# GPS_Board_Rev_B.net
KiCad netlist of a schematic drawn in EAGLE
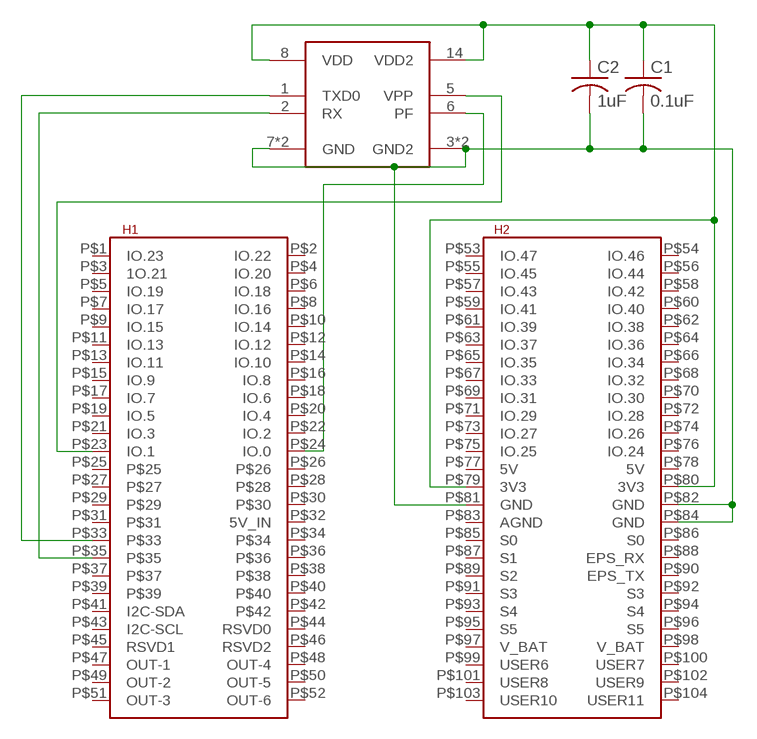
[diagram p0: schematic, sheet 1]

(export (version "E")
  (design (tool "Eeschema 10.0.6"))
  (components
    (comp (ref "C1")
      (value "0.1uF")
      (footprint "eagle-import:C0603")
      (libsource (lib "eagle-import") (part "C-USC0603"))
    )
    (comp (ref "C2")
      (value "1uF")
      (footprint "eagle-import:C0603")
      (libsource (lib "eagle-import") (part "C-USC0603"))
    )
    (comp (ref "U$1")
      (value "PINAVL1")
      (footprint "eagle-import:PINAV-L1")
      (libsource (lib "eagle-import") (part "PINAVL1"))
    )
    (comp (ref "U$2")
      (value "PC104")
      (footprint "eagle-import:PC104")
      (libsource (lib "eagle-import") (part "PC104"))
    )
  )
  (nets
    (net (code "1") (name "Net-(C1-Pad2)") (class "Default")
      (node (ref "C1") (pin "2") (pinfunction "2_2") (pintype "passive"))
      (node (ref "C2") (pin "2") (pinfunction "2_2") (pintype "passive"))
      (node (ref "U$1") (pin "15") (pinfunction "GND2_15") (pintype "bidirectional"))
      (node (ref "U$1") (pin "16") (pinfunction "GND_16") (pintype "bidirectional"))
      (node (ref "U$1") (pin "3") (pinfunction "GND2_3") (pintype "bidirectional"))
      (node (ref "U$1") (pin "7") (pinfunction "GND_7") (pintype "bidirectional"))
      (node (ref "U$2") (pin "P$81") (pinfunction "GND_P$81") (pintype "bidirectional"))
      (node (ref "U$2") (pin "P$82") (pinfunction "GND_P$82") (pintype "bidirectional"))
      (node (ref "U$2") (pin "P$84") (pinfunction "GND_P$84") (pintype "bidirectional"))
    )
    (net (code "2") (name "Net-(U$1-PF)") (class "Default")
      (node (ref "U$1") (pin "6") (pinfunction "PF_6") (pintype "bidirectional"))
      (node (ref "U$2") (pin "P$24") (pinfunction "IO.0_P$24") (pintype "bidirectional"))
    )
    (net (code "3") (name "Net-(U$1-RX)") (class "Default")
      (node (ref "U$1") (pin "2") (pinfunction "RX_2") (pintype "bidirectional"))
      (node (ref "U$2") (pin "P$35") (pinfunction "P$35_P$35") (pintype "bidirectional"))
    )
    (net (code "4") (name "Net-(U$1-TXD0)") (class "Default")
      (node (ref "U$1") (pin "1") (pinfunction "TXD0_1") (pintype "bidirectional"))
      (node (ref "U$2") (pin "P$33") (pinfunction "P$33_P$33") (pintype "bidirectional"))
    )
    (net (code "5") (name "Net-(U$1-VDD)") (class "Default")
      (node (ref "C1") (pin "1") (pinfunction "1_1") (pintype "passive"))
      (node (ref "C2") (pin "1") (pinfunction "1_1") (pintype "passive"))
      (node (ref "U$1") (pin "14") (pinfunction "VDD2_14") (pintype "bidirectional"))
      (node (ref "U$1") (pin "8") (pinfunction "VDD_8") (pintype "bidirectional"))
      (node (ref "U$2") (pin "P$79") (pinfunction "3V3_P$79") (pintype "bidirectional"))
      (node (ref "U$2") (pin "P$80") (pinfunction "3V3_P$80") (pintype "bidirectional"))
    )
    (net (code "6") (name "Net-(U$1-VPP)") (class "Default")
      (node (ref "U$1") (pin "5") (pinfunction "VPP_5") (pintype "bidirectional"))
      (node (ref "U$2") (pin "P$23") (pinfunction "IO.1_P$23") (pintype "bidirectional"))
    )
    (net (code "7") (name "unconnected-(U$2-1O.21-PadP$3)") (class "Default")
      (node (ref "U$2") (pin "P$3") (pinfunction "1O.21_P$3") (pintype "bidirectional"))
    )
    (net (code "8") (name "unconnected-(U$2-5V-PadP$77)") (class "Default")
      (node (ref "U$2") (pin "P$77") (pinfunction "5V_P$77") (pintype "bidirectional"))
    )
    (net (code "9") (name "unconnected-(U$2-5V-PadP$78)") (class "Default")
      (node (ref "U$2") (pin "P$78") (pinfunction "5V_P$78") (pintype "bidirectional"))
    )
    (net (code "10") (name "unconnected-(U$2-5V_IN-PadP$32)") (class "Default")
      (node (ref "U$2") (pin "P$32") (pinfunction "5V_IN_P$32") (pintype "bidirectional"))
    )
    (net (code "11") (name "unconnected-(U$2-AGND-PadP$83)") (class "Default")
      (node (ref "U$2") (pin "P$83") (pinfunction "AGND_P$83") (pintype "bidirectional"))
    )
    (net (code "12") (name "unconnected-(U$2-EPS_RX-PadP$88)") (class "Default")
      (node (ref "U$2") (pin "P$88") (pinfunction "EPS_RX_P$88") (pintype "bidirectional"))
    )
    (net (code "13") (name "unconnected-(U$2-EPS_TX-PadP$90)") (class "Default")
      (node (ref "U$2") (pin "P$90") (pinfunction "EPS_TX_P$90") (pintype "bidirectional"))
    )
    (net (code "14") (name "unconnected-(U$2-I2C-SCL-PadP$43)") (class "Default")
      (node (ref "U$2") (pin "P$43") (pinfunction "I2C-SCL_P$43") (pintype "bidirectional"))
    )
    (net (code "15") (name "unconnected-(U$2-I2C-SDA-PadP$41)") (class "Default")
      (node (ref "U$2") (pin "P$41") (pinfunction "I2C-SDA_P$41") (pintype "bidirectional"))
    )
    (net (code "16") (name "unconnected-(U$2-IO.2-PadP$22)") (class "Default")
      (node (ref "U$2") (pin "P$22") (pinfunction "IO.2_P$22") (pintype "bidirectional"))
    )
    (net (code "17") (name "unconnected-(U$2-IO.3-PadP$21)") (class "Default")
      (node (ref "U$2") (pin "P$21") (pinfunction "IO.3_P$21") (pintype "bidirectional"))
    )
    (net (code "18") (name "unconnected-(U$2-IO.4-PadP$20)") (class "Default")
      (node (ref "U$2") (pin "P$20") (pinfunction "IO.4_P$20") (pintype "bidirectional"))
    )
    (net (code "19") (name "unconnected-(U$2-IO.5-PadP$19)") (class "Default")
      (node (ref "U$2") (pin "P$19") (pinfunction "IO.5_P$19") (pintype "bidirectional"))
    )
    (net (code "20") (name "unconnected-(U$2-IO.6-PadP$18)") (class "Default")
      (node (ref "U$2") (pin "P$18") (pinfunction "IO.6_P$18") (pintype "bidirectional"))
    )
    (net (code "21") (name "unconnected-(U$2-IO.7-PadP$17)") (class "Default")
      (node (ref "U$2") (pin "P$17") (pinfunction "IO.7_P$17") (pintype "bidirectional"))
    )
    (net (code "22") (name "unconnected-(U$2-IO.8-PadP$16)") (class "Default")
      (node (ref "U$2") (pin "P$16") (pinfunction "IO.8_P$16") (pintype "bidirectional"))
    )
    (net (code "23") (name "unconnected-(U$2-IO.9-PadP$15)") (class "Default")
      (node (ref "U$2") (pin "P$15") (pinfunction "IO.9_P$15") (pintype "bidirectional"))
    )
    (net (code "24") (name "unconnected-(U$2-IO.10-PadP$14)") (class "Default")
      (node (ref "U$2") (pin "P$14") (pinfunction "IO.10_P$14") (pintype "bidirectional"))
    )
    (net (code "25") (name "unconnected-(U$2-IO.11-PadP$13)") (class "Default")
      (node (ref "U$2") (pin "P$13") (pinfunction "IO.11_P$13") (pintype "bidirectional"))
    )
    (net (code "26") (name "unconnected-(U$2-IO.12-PadP$12)") (class "Default")
      (node (ref "U$2") (pin "P$12") (pinfunction "IO.12_P$12") (pintype "bidirectional"))
    )
    (net (code "27") (name "unconnected-(U$2-IO.13-PadP$11)") (class "Default")
      (node (ref "U$2") (pin "P$11") (pinfunction "IO.13_P$11") (pintype "bidirectional"))
    )
    (net (code "28") (name "unconnected-(U$2-IO.14-PadP$10)") (class "Default")
      (node (ref "U$2") (pin "P$10") (pinfunction "IO.14_P$10") (pintype "bidirectional"))
    )
    (net (code "29") (name "unconnected-(U$2-IO.15-PadP$9)") (class "Default")
      (node (ref "U$2") (pin "P$9") (pinfunction "IO.15_P$9") (pintype "bidirectional"))
    )
    (net (code "30") (name "unconnected-(U$2-IO.16-PadP$8)") (class "Default")
      (node (ref "U$2") (pin "P$8") (pinfunction "IO.16_P$8") (pintype "bidirectional"))
    )
    (net (code "31") (name "unconnected-(U$2-IO.17-PadP$7)") (class "Default")
      (node (ref "U$2") (pin "P$7") (pinfunction "IO.17_P$7") (pintype "bidirectional"))
    )
    (net (code "32") (name "unconnected-(U$2-IO.18-PadP$6)") (class "Default")
      (node (ref "U$2") (pin "P$6") (pinfunction "IO.18_P$6") (pintype "bidirectional"))
    )
    (net (code "33") (name "unconnected-(U$2-IO.19-PadP$5)") (class "Default")
      (node (ref "U$2") (pin "P$5") (pinfunction "IO.19_P$5") (pintype "bidirectional"))
    )
    (net (code "34") (name "unconnected-(U$2-IO.20-PadP$4)") (class "Default")
      (node (ref "U$2") (pin "P$4") (pinfunction "IO.20_P$4") (pintype "bidirectional"))
    )
    (net (code "35") (name "unconnected-(U$2-IO.22-PadP$2)") (class "Default")
      (node (ref "U$2") (pin "P$2") (pinfunction "IO.22_P$2") (pintype "bidirectional"))
    )
    (net (code "36") (name "unconnected-(U$2-IO.23-PadP$1)") (class "Default")
      (node (ref "U$2") (pin "P$1") (pinfunction "IO.23_P$1") (pintype "bidirectional"))
    )
    (net (code "37") (name "unconnected-(U$2-IO.24-PadP$76)") (class "Default")
      (node (ref "U$2") (pin "P$76") (pinfunction "IO.24_P$76") (pintype "bidirectional"))
    )
    (net (code "38") (name "unconnected-(U$2-IO.25-PadP$75)") (class "Default")
      (node (ref "U$2") (pin "P$75") (pinfunction "IO.25_P$75") (pintype "bidirectional"))
    )
    (net (code "39") (name "unconnected-(U$2-IO.26-PadP$74)") (class "Default")
      (node (ref "U$2") (pin "P$74") (pinfunction "IO.26_P$74") (pintype "bidirectional"))
    )
    (net (code "40") (name "unconnected-(U$2-IO.27-PadP$73)") (class "Default")
      (node (ref "U$2") (pin "P$73") (pinfunction "IO.27_P$73") (pintype "bidirectional"))
    )
    (net (code "41") (name "unconnected-(U$2-IO.28-PadP$72)") (class "Default")
      (node (ref "U$2") (pin "P$72") (pinfunction "IO.28_P$72") (pintype "bidirectional"))
    )
    (net (code "42") (name "unconnected-(U$2-IO.29-PadP$71)") (class "Default")
      (node (ref "U$2") (pin "P$71") (pinfunction "IO.29_P$71") (pintype "bidirectional"))
    )
    (net (code "43") (name "unconnected-(U$2-IO.30-PadP$70)") (class "Default")
      (node (ref "U$2") (pin "P$70") (pinfunction "IO.30_P$70") (pintype "bidirectional"))
    )
    (net (code "44") (name "unconnected-(U$2-IO.31-PadP$69)") (class "Default")
      (node (ref "U$2") (pin "P$69") (pinfunction "IO.31_P$69") (pintype "bidirectional"))
    )
    (net (code "45") (name "unconnected-(U$2-IO.32-PadP$68)") (class "Default")
      (node (ref "U$2") (pin "P$68") (pinfunction "IO.32_P$68") (pintype "bidirectional"))
    )
    (net (code "46") (name "unconnected-(U$2-IO.33-PadP$67)") (class "Default")
      (node (ref "U$2") (pin "P$67") (pinfunction "IO.33_P$67") (pintype "bidirectional"))
    )
    (net (code "47") (name "unconnected-(U$2-IO.34-PadP$66)") (class "Default")
      (node (ref "U$2") (pin "P$66") (pinfunction "IO.34_P$66") (pintype "bidirectional"))
    )
    (net (code "48") (name "unconnected-(U$2-IO.35-PadP$65)") (class "Default")
      (node (ref "U$2") (pin "P$65") (pinfunction "IO.35_P$65") (pintype "bidirectional"))
    )
    (net (code "49") (name "unconnected-(U$2-IO.36-PadP$64)") (class "Default")
      (node (ref "U$2") (pin "P$64") (pinfunction "IO.36_P$64") (pintype "bidirectional"))
    )
    (net (code "50") (name "unconnected-(U$2-IO.37-PadP$63)") (class "Default")
      (node (ref "U$2") (pin "P$63") (pinfunction "IO.37_P$63") (pintype "bidirectional"))
    )
    (net (code "51") (name "unconnected-(U$2-IO.38-PadP$62)") (class "Default")
      (node (ref "U$2") (pin "P$62") (pinfunction "IO.38_P$62") (pintype "bidirectional"))
    )
    (net (code "52") (name "unconnected-(U$2-IO.39-PadP$61)") (class "Default")
      (node (ref "U$2") (pin "P$61") (pinfunction "IO.39_P$61") (pintype "bidirectional"))
    )
    (net (code "53") (name "unconnected-(U$2-IO.40-PadP$60)") (class "Default")
      (node (ref "U$2") (pin "P$60") (pinfunction "IO.40_P$60") (pintype "bidirectional"))
    )
    (net (code "54") (name "unconnected-(U$2-IO.41-PadP$59)") (class "Default")
      (node (ref "U$2") (pin "P$59") (pinfunction "IO.41_P$59") (pintype "bidirectional"))
    )
    (net (code "55") (name "unconnected-(U$2-IO.42-PadP$58)") (class "Default")
      (node (ref "U$2") (pin "P$58") (pinfunction "IO.42_P$58") (pintype "bidirectional"))
    )
    (net (code "56") (name "unconnected-(U$2-IO.43-PadP$57)") (class "Default")
      (node (ref "U$2") (pin "P$57") (pinfunction "IO.43_P$57") (pintype "bidirectional"))
    )
    (net (code "57") (name "unconnected-(U$2-IO.44-PadP$56)") (class "Default")
      (node (ref "U$2") (pin "P$56") (pinfunction "IO.44_P$56") (pintype "bidirectional"))
    )
    (net (code "58") (name "unconnected-(U$2-IO.45-PadP$55)") (class "Default")
      (node (ref "U$2") (pin "P$55") (pinfunction "IO.45_P$55") (pintype "bidirectional"))
    )
    (net (code "59") (name "unconnected-(U$2-IO.46-PadP$54)") (class "Default")
      (node (ref "U$2") (pin "P$54") (pinfunction "IO.46_P$54") (pintype "bidirectional"))
    )
    (net (code "60") (name "unconnected-(U$2-IO.47-PadP$53)") (class "Default")
      (node (ref "U$2") (pin "P$53") (pinfunction "IO.47_P$53") (pintype "bidirectional"))
    )
    (net (code "61") (name "unconnected-(U$2-OUT-1-PadP$47)") (class "Default")
      (node (ref "U$2") (pin "P$47") (pinfunction "OUT-1_P$47") (pintype "bidirectional"))
    )
    (net (code "62") (name "unconnected-(U$2-OUT-2-PadP$49)") (class "Default")
      (node (ref "U$2") (pin "P$49") (pinfunction "OUT-2_P$49") (pintype "bidirectional"))
    )
    (net (code "63") (name "unconnected-(U$2-OUT-3-PadP$51)") (class "Default")
      (node (ref "U$2") (pin "P$51") (pinfunction "OUT-3_P$51") (pintype "bidirectional"))
    )
    (net (code "64") (name "unconnected-(U$2-OUT-4-PadP$48)") (class "Default")
      (node (ref "U$2") (pin "P$48") (pinfunction "OUT-4_P$48") (pintype "bidirectional"))
    )
    (net (code "65") (name "unconnected-(U$2-OUT-5-PadP$50)") (class "Default")
      (node (ref "U$2") (pin "P$50") (pinfunction "OUT-5_P$50") (pintype "bidirectional"))
    )
    (net (code "66") (name "unconnected-(U$2-OUT-6-PadP$52)") (class "Default")
      (node (ref "U$2") (pin "P$52") (pinfunction "OUT-6_P$52") (pintype "bidirectional"))
    )
    (net (code "67") (name "unconnected-(U$2-PadP$25)") (class "Default")
      (node (ref "U$2") (pin "P$25") (pinfunction "P$25_P$25") (pintype "bidirectional"))
    )
    (net (code "68") (name "unconnected-(U$2-PadP$26)") (class "Default")
      (node (ref "U$2") (pin "P$26") (pinfunction "P$26_P$26") (pintype "bidirectional"))
    )
    (net (code "69") (name "unconnected-(U$2-PadP$27)") (class "Default")
      (node (ref "U$2") (pin "P$27") (pinfunction "P$27_P$27") (pintype "bidirectional"))
    )
    (net (code "70") (name "unconnected-(U$2-PadP$28)") (class "Default")
      (node (ref "U$2") (pin "P$28") (pinfunction "P$28_P$28") (pintype "bidirectional"))
    )
    (net (code "71") (name "unconnected-(U$2-PadP$29)") (class "Default")
      (node (ref "U$2") (pin "P$29") (pinfunction "P$29_P$29") (pintype "bidirectional"))
    )
    (net (code "72") (name "unconnected-(U$2-PadP$30)") (class "Default")
      (node (ref "U$2") (pin "P$30") (pinfunction "P$30_P$30") (pintype "bidirectional"))
    )
    (net (code "73") (name "unconnected-(U$2-PadP$31)") (class "Default")
      (node (ref "U$2") (pin "P$31") (pinfunction "P$31_P$31") (pintype "bidirectional"))
    )
    (net (code "74") (name "unconnected-(U$2-PadP$34)") (class "Default")
      (node (ref "U$2") (pin "P$34") (pinfunction "P$34_P$34") (pintype "bidirectional"))
    )
    (net (code "75") (name "unconnected-(U$2-PadP$36)") (class "Default")
      (node (ref "U$2") (pin "P$36") (pinfunction "P$36_P$36") (pintype "bidirectional"))
    )
    (net (code "76") (name "unconnected-(U$2-PadP$37)") (class "Default")
      (node (ref "U$2") (pin "P$37") (pinfunction "P$37_P$37") (pintype "bidirectional"))
    )
    (net (code "77") (name "unconnected-(U$2-PadP$38)") (class "Default")
      (node (ref "U$2") (pin "P$38") (pinfunction "P$38_P$38") (pintype "bidirectional"))
    )
    (net (code "78") (name "unconnected-(U$2-PadP$39)") (class "Default")
      (node (ref "U$2") (pin "P$39") (pinfunction "P$39_P$39") (pintype "bidirectional"))
    )
    (net (code "79") (name "unconnected-(U$2-PadP$40)") (class "Default")
      (node (ref "U$2") (pin "P$40") (pinfunction "P$40_P$40") (pintype "bidirectional"))
    )
    (net (code "80") (name "unconnected-(U$2-PadP$42)") (class "Default")
      (node (ref "U$2") (pin "P$42") (pinfunction "P$42_P$42") (pintype "bidirectional"))
    )
    (net (code "81") (name "unconnected-(U$2-RSVD0-PadP$44)") (class "Default")
      (node (ref "U$2") (pin "P$44") (pinfunction "RSVD0_P$44") (pintype "bidirectional"))
    )
    (net (code "82") (name "unconnected-(U$2-RSVD1-PadP$45)") (class "Default")
      (node (ref "U$2") (pin "P$45") (pinfunction "RSVD1_P$45") (pintype "bidirectional"))
    )
    (net (code "83") (name "unconnected-(U$2-RSVD2-PadP$46)") (class "Default")
      (node (ref "U$2") (pin "P$46") (pinfunction "RSVD2_P$46") (pintype "bidirectional"))
    )
    (net (code "84") (name "unconnected-(U$2-S0-PadP$85)") (class "Default")
      (node (ref "U$2") (pin "P$85") (pinfunction "S0_P$85") (pintype "bidirectional"))
    )
    (net (code "85") (name "unconnected-(U$2-S0-PadP$86)") (class "Default")
      (node (ref "U$2") (pin "P$86") (pinfunction "S0_P$86") (pintype "bidirectional"))
    )
    (net (code "86") (name "unconnected-(U$2-S1-PadP$87)") (class "Default")
      (node (ref "U$2") (pin "P$87") (pinfunction "S1_P$87") (pintype "bidirectional"))
    )
    (net (code "87") (name "unconnected-(U$2-S2-PadP$89)") (class "Default")
      (node (ref "U$2") (pin "P$89") (pinfunction "S2_P$89") (pintype "bidirectional"))
    )
    (net (code "88") (name "unconnected-(U$2-S3-PadP$91)") (class "Default")
      (node (ref "U$2") (pin "P$91") (pinfunction "S3_P$91") (pintype "bidirectional"))
    )
    (net (code "89") (name "unconnected-(U$2-S3-PadP$92)") (class "Default")
      (node (ref "U$2") (pin "P$92") (pinfunction "S3_P$92") (pintype "bidirectional"))
    )
    (net (code "90") (name "unconnected-(U$2-S4-PadP$93)") (class "Default")
      (node (ref "U$2") (pin "P$93") (pinfunction "S4_P$93") (pintype "bidirectional"))
    )
    (net (code "91") (name "unconnected-(U$2-S4-PadP$94)") (class "Default")
      (node (ref "U$2") (pin "P$94") (pinfunction "S4_P$94") (pintype "bidirectional"))
    )
    (net (code "92") (name "unconnected-(U$2-S5-PadP$95)") (class "Default")
      (node (ref "U$2") (pin "P$95") (pinfunction "S5_P$95") (pintype "bidirectional"))
    )
    (net (code "93") (name "unconnected-(U$2-S5-PadP$96)") (class "Default")
      (node (ref "U$2") (pin "P$96") (pinfunction "S5_P$96") (pintype "bidirectional"))
    )
    (net (code "94") (name "unconnected-(U$2-USER6-PadP$99)") (class "Default")
      (node (ref "U$2") (pin "P$99") (pinfunction "USER6_P$99") (pintype "bidirectional"))
    )
    (net (code "95") (name "unconnected-(U$2-USER7-PadP$100)") (class "Default")
      (node (ref "U$2") (pin "P$100") (pinfunction "USER7_P$100") (pintype "bidirectional"))
    )
    (net (code "96") (name "unconnected-(U$2-USER8-PadP$101)") (class "Default")
      (node (ref "U$2") (pin "P$101") (pinfunction "USER8_P$101") (pintype "bidirectional"))
    )
    (net (code "97") (name "unconnected-(U$2-USER9-PadP$102)") (class "Default")
      (node (ref "U$2") (pin "P$102") (pinfunction "USER9_P$102") (pintype "bidirectional"))
    )
    (net (code "98") (name "unconnected-(U$2-USER10-PadP$103)") (class "Default")
      (node (ref "U$2") (pin "P$103") (pinfunction "USER10_P$103") (pintype "bidirectional"))
    )
    (net (code "99") (name "unconnected-(U$2-USER11-PadP$104)") (class "Default")
      (node (ref "U$2") (pin "P$104") (pinfunction "USER11_P$104") (pintype "bidirectional"))
    )
    (net (code "100") (name "unconnected-(U$2-V_BAT-PadP$97)") (class "Default")
      (node (ref "U$2") (pin "P$97") (pinfunction "V_BAT_P$97") (pintype "bidirectional"))
    )
    (net (code "101") (name "unconnected-(U$2-V_BAT-PadP$98)") (class "Default")
      (node (ref "U$2") (pin "P$98") (pinfunction "V_BAT_P$98") (pintype "bidirectional"))
    )
  )
)
